# bebox_spritzer.net
KiCad netlist of a schematic drawn in EAGLE
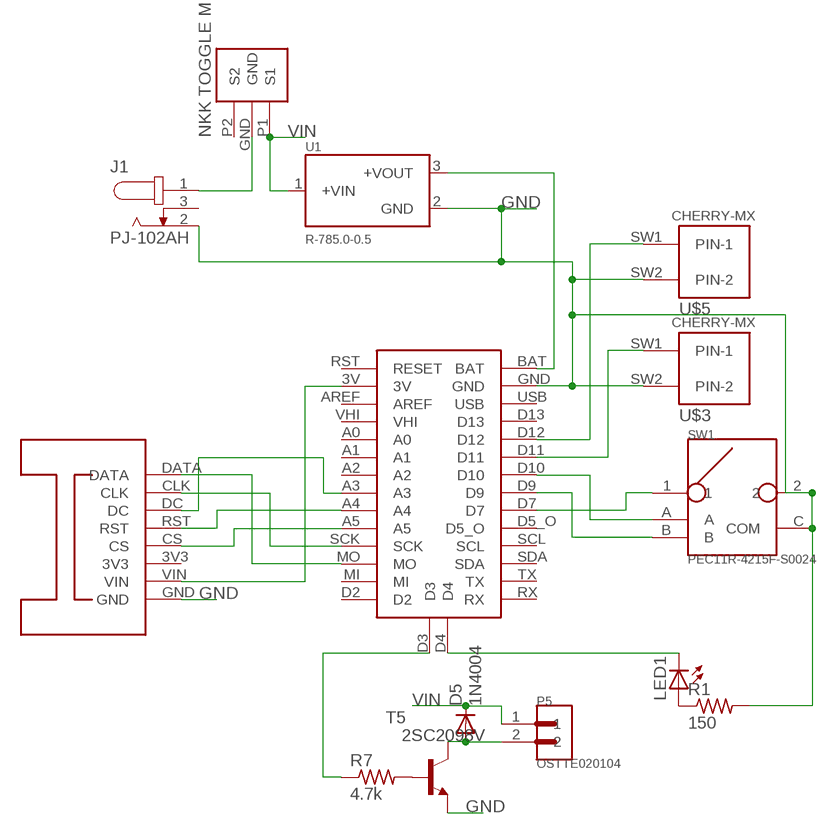
[diagram p0: schematic, sheet 1]

(export (version "E")
  (design (tool "Eeschema 10.0.6"))
  (components
    (comp (ref "D5")
      (value "1N4004")
      (footprint "eagle-import:DO41-10")
      (libsource (lib "eagle-import") (part "1N4004"))
    )
    (comp (ref "J1")
      (value "PJ-102AH")
      (footprint "eagle-import:CUI_PJ-102AH")
      (fields (field (name "MANUFACTURER") "CUI INC"))
      (libsource (lib "eagle-import") (part "PJ-102AH"))
    )
    (comp (ref "LED1")
      (value "LED5MM")
      (footprint "eagle-import:LED5MM")
      (libsource (lib "eagle-import") (part "LED5MM"))
    )
    (comp (ref "P5")
      (value "OSTTE020104")
      (footprint "eagle-import:OST_OSTTE020104")
      (fields (field (name "DIGI-KEY_PART_NUMBER") "ED2740-ND") (field (name "MF") "On Shore"))
      (libsource (lib "eagle-import") (part "OSTTE020104"))
    )
    (comp (ref "R1")
      (value "150")
      (footprint "eagle-import:0207_10")
      (libsource (lib "eagle-import") (part "R-US_0207/10"))
    )
    (comp (ref "R7")
      (value "4.7k")
      (footprint "eagle-import:0207_10")
      (libsource (lib "eagle-import") (part "R-US_0207/10"))
    )
    (comp (ref "SW1")
      (value "PEC11R-4215F-S0024")
      (footprint "eagle-import:SW_PEC11R-4215F-S0024")
      (fields (field (name "MF") "Bourns"))
      (libsource (lib "eagle-import") (part "PEC11R-4215F-S0024"))
    )
    (comp (ref "T5")
      (value "2SC2098V")
      (footprint "eagle-import:TO220AV")
      (libsource (lib "eagle-import") (part "2SC2098V"))
    )
    (comp (ref "U$1")
      (value "ITSYBITSYM4")
      (footprint "eagle-import:ITSYBITSYM4")
      (libsource (lib "eagle-import") (part "ITSYBITSYM4"))
    )
    (comp (ref "U$2")
      (value "OLED_128X64")
      (footprint "eagle-import:OLED_128X64")
      (libsource (lib "eagle-import") (part "OLED_128X64"))
    )
    (comp (ref "U$3")
      (value "CHERRY-MX")
      (footprint "eagle-import:CHERRY-MX")
      (libsource (lib "eagle-import") (part "CHERRY-MX"))
    )
    (comp (ref "U$4")
      (value "NKK_M2012S2A2A30")
      (footprint "eagle-import:NKK_M2012S2A2A30")
      (libsource (lib "eagle-import") (part "NKK_M2012S2A2A30"))
    )
    (comp (ref "U$5")
      (value "CHERRY-MX")
      (footprint "eagle-import:CHERRY-MX")
      (libsource (lib "eagle-import") (part "CHERRY-MX"))
    )
    (comp (ref "U1")
      (value "R-785.0-0.5")
      (footprint "eagle-import:RECOM_R-785.0-0.5")
      (fields (field (name "DIGI-KEY_PART_NUMBER") "945-1037-ND") (field (name "MF") "Recom Power"))
      (libsource (lib "eagle-import") (part "R-785.0-0.5"))
    )
  )
  (nets
    (net (code "1") (name "/GND") (class "Default")
      (node (ref "J1") (pin "2") (pinfunction "2_2") (pintype "passive"))
      (node (ref "R1") (pin "2") (pinfunction "2_2") (pintype "passive"))
      (node (ref "SW1") (pin "2") (pinfunction "2_2") (pintype "passive"))
      (node (ref "SW1") (pin "C") (pinfunction "COM_C") (pintype "passive"))
      (node (ref "T5") (pin "3") (pinfunction "E_3") (pintype "passive"))
      (node (ref "U$1") (pin "GND") (pinfunction "GND_GND") (pintype "bidirectional"))
      (node (ref "U$2") (pin "GND") (pinfunction "GND_GND") (pintype "bidirectional"))
      (node (ref "U$3") (pin "SW2") (pinfunction "PIN-2_SW2") (pintype "bidirectional"))
      (node (ref "U$5") (pin "SW2") (pinfunction "PIN-2_SW2") (pintype "bidirectional"))
      (node (ref "U1") (pin "2") (pinfunction "GND_2") (pintype "power_in"))
    )
    (net (code "2") (name "/VIN") (class "Default")
      (node (ref "D5") (pin "C") (pinfunction "C_C") (pintype "passive"))
      (node (ref "P5") (pin "1") (pinfunction "1_1") (pintype "passive"))
      (node (ref "U$4") (pin "P1") (pinfunction "S1_P1") (pintype "bidirectional"))
      (node (ref "U1") (pin "1") (pinfunction "+VIN_1") (pintype "input"))
    )
    (net (code "3") (name "Net-(J1-Pad1)") (class "Default")
      (node (ref "J1") (pin "1") (pinfunction "1_1") (pintype "passive"))
      (node (ref "U$4") (pin "GND") (pinfunction "GND_GND") (pintype "bidirectional"))
    )
    (net (code "4") (name "Net-(LED1-C)") (class "Default")
      (node (ref "LED1") (pin "K") (pinfunction "C_K") (pintype "passive"))
      (node (ref "U$1") (pin "D4") (pinfunction "D4_D4") (pintype "bidirectional"))
    )
    (net (code "5") (name "Net-(LED1-PadA)") (class "Default")
      (node (ref "LED1") (pin "A") (pinfunction "A_A") (pintype "passive"))
      (node (ref "R1") (pin "1") (pinfunction "1_1") (pintype "passive"))
    )
    (net (code "6") (name "Net-(R7-Pad1)") (class "Default")
      (node (ref "R7") (pin "1") (pinfunction "1_1") (pintype "passive"))
      (node (ref "U$1") (pin "D3") (pinfunction "D3_D3") (pintype "bidirectional"))
    )
    (net (code "7") (name "Net-(SW1-Pad1)") (class "Default")
      (node (ref "SW1") (pin "1") (pinfunction "1_1") (pintype "passive"))
      (node (ref "U$1") (pin "D7") (pinfunction "D7_D7") (pintype "bidirectional"))
    )
    (net (code "8") (name "Net-(SW1-PadA)") (class "Default")
      (node (ref "SW1") (pin "A") (pinfunction "A_A") (pintype "passive"))
      (node (ref "U$1") (pin "D10") (pinfunction "D10_D10") (pintype "bidirectional"))
    )
    (net (code "9") (name "Net-(SW1-PadB)") (class "Default")
      (node (ref "SW1") (pin "B") (pinfunction "B_B") (pintype "passive"))
      (node (ref "U$1") (pin "D9") (pinfunction "D9_D9") (pintype "bidirectional"))
    )
    (net (code "10") (name "Net-(T5-B)") (class "Default")
      (node (ref "R7") (pin "2") (pinfunction "2_2") (pintype "passive"))
      (node (ref "T5") (pin "1") (pinfunction "B_1") (pintype "passive"))
    )
    (net (code "11") (name "Net-(T5-C)") (class "Default")
      (node (ref "D5") (pin "A") (pinfunction "A_A") (pintype "passive"))
      (node (ref "P5") (pin "2") (pinfunction "2_2") (pintype "passive"))
      (node (ref "T5") (pin "2") (pinfunction "C_2") (pintype "passive"))
    )
    (net (code "12") (name "Net-(U$1-Pad3V)") (class "Default")
      (node (ref "U$1") (pin "3V") (pinfunction "3V_3V") (pintype "bidirectional"))
      (node (ref "U$2") (pin "VIN") (pinfunction "VIN_VIN") (pintype "bidirectional"))
    )
    (net (code "13") (name "Net-(U$1-PadA3)") (class "Default")
      (node (ref "U$1") (pin "A3") (pinfunction "A3_A3") (pintype "bidirectional"))
      (node (ref "U$2") (pin "DC") (pinfunction "DC_DC") (pintype "bidirectional"))
    )
    (net (code "14") (name "Net-(U$1-PadA4)") (class "Default")
      (node (ref "U$1") (pin "A4") (pinfunction "A4_A4") (pintype "bidirectional"))
      (node (ref "U$2") (pin "RST") (pinfunction "RST_RST") (pintype "bidirectional"))
    )
    (net (code "15") (name "Net-(U$1-PadA5)") (class "Default")
      (node (ref "U$1") (pin "A5") (pinfunction "A5_A5") (pintype "bidirectional"))
      (node (ref "U$2") (pin "CS") (pinfunction "CS_CS") (pintype "bidirectional"))
    )
    (net (code "16") (name "Net-(U$1-PadMO)") (class "Default")
      (node (ref "U$1") (pin "MO") (pinfunction "MO_MO") (pintype "bidirectional"))
      (node (ref "U$2") (pin "DATA") (pinfunction "DATA_DATA") (pintype "bidirectional"))
    )
    (net (code "17") (name "Net-(U$1-PadSCK)") (class "Default")
      (node (ref "U$1") (pin "SCK") (pinfunction "SCK_SCK") (pintype "bidirectional"))
      (node (ref "U$2") (pin "CLK") (pinfunction "CLK_CLK") (pintype "bidirectional"))
    )
    (net (code "18") (name "Net-(U$3-PIN-1)") (class "Default")
      (node (ref "U$1") (pin "D11") (pinfunction "D11_D11") (pintype "bidirectional"))
      (node (ref "U$3") (pin "SW1") (pinfunction "PIN-1_SW1") (pintype "bidirectional"))
    )
    (net (code "19") (name "Net-(U$5-PIN-1)") (class "Default")
      (node (ref "U$1") (pin "D12") (pinfunction "D12_D12") (pintype "bidirectional"))
      (node (ref "U$5") (pin "SW1") (pinfunction "PIN-1_SW1") (pintype "bidirectional"))
    )
    (net (code "20") (name "Net-(U1-+VOUT)") (class "Default")
      (node (ref "U$1") (pin "BAT") (pinfunction "BAT_BAT") (pintype "bidirectional"))
      (node (ref "U1") (pin "3") (pinfunction "+VOUT_3") (pintype "output"))
    )
    (net (code "21") (name "unconnected-(J1-Pad3)") (class "Default")
      (node (ref "J1") (pin "3") (pinfunction "3_3") (pintype "passive"))
    )
    (net (code "22") (name "unconnected-(U$1-PadA0)") (class "Default")
      (node (ref "U$1") (pin "A0") (pinfunction "A0_A0") (pintype "bidirectional"))
    )
    (net (code "23") (name "unconnected-(U$1-PadA1)") (class "Default")
      (node (ref "U$1") (pin "A1") (pinfunction "A1_A1") (pintype "bidirectional"))
    )
    (net (code "24") (name "unconnected-(U$1-PadA2)") (class "Default")
      (node (ref "U$1") (pin "A2") (pinfunction "A2_A2") (pintype "bidirectional"))
    )
    (net (code "25") (name "unconnected-(U$1-PadAREF)") (class "Default")
      (node (ref "U$1") (pin "AREF") (pinfunction "AREF_AREF") (pintype "bidirectional"))
    )
    (net (code "26") (name "unconnected-(U$1-PadD2)") (class "Default")
      (node (ref "U$1") (pin "D2") (pinfunction "D2_D2") (pintype "bidirectional"))
    )
    (net (code "27") (name "unconnected-(U$1-PadD5_O)") (class "Default")
      (node (ref "U$1") (pin "D5_O") (pinfunction "D5_O_D5_O") (pintype "bidirectional"))
    )
    (net (code "28") (name "unconnected-(U$1-PadD13)") (class "Default")
      (node (ref "U$1") (pin "D13") (pinfunction "D13_D13") (pintype "bidirectional"))
    )
    (net (code "29") (name "unconnected-(U$1-PadMI)") (class "Default")
      (node (ref "U$1") (pin "MI") (pinfunction "MI_MI") (pintype "bidirectional"))
    )
    (net (code "30") (name "unconnected-(U$1-PadRX)") (class "Default")
      (node (ref "U$1") (pin "RX") (pinfunction "RX_RX") (pintype "bidirectional"))
    )
    (net (code "31") (name "unconnected-(U$1-PadSCL)") (class "Default")
      (node (ref "U$1") (pin "SCL") (pinfunction "SCL_SCL") (pintype "bidirectional"))
    )
    (net (code "32") (name "unconnected-(U$1-PadSDA)") (class "Default")
      (node (ref "U$1") (pin "SDA") (pinfunction "SDA_SDA") (pintype "bidirectional"))
    )
    (net (code "33") (name "unconnected-(U$1-PadTX)") (class "Default")
      (node (ref "U$1") (pin "TX") (pinfunction "TX_TX") (pintype "bidirectional"))
    )
    (net (code "34") (name "unconnected-(U$1-PadUSB)") (class "Default")
      (node (ref "U$1") (pin "USB") (pinfunction "USB_USB") (pintype "bidirectional"))
    )
    (net (code "35") (name "unconnected-(U$1-PadVHI)") (class "Default")
      (node (ref "U$1") (pin "VHI") (pinfunction "VHI_VHI") (pintype "bidirectional"))
    )
    (net (code "36") (name "unconnected-(U$1-RESET-PadRST)") (class "Default")
      (node (ref "U$1") (pin "RST") (pinfunction "RESET_RST") (pintype "bidirectional"))
    )
    (net (code "37") (name "unconnected-(U$2-Pad3V3)") (class "Default")
      (node (ref "U$2") (pin "3V3") (pinfunction "3V3_3V3") (pintype "bidirectional"))
    )
    (net (code "38") (name "unconnected-(U$4-S2-PadP2)") (class "Default")
      (node (ref "U$4") (pin "P2") (pinfunction "S2_P2") (pintype "bidirectional"))
    )
  )
)
